# PCB1.net
KiCad netlist of a schematic drawn in EAGLE
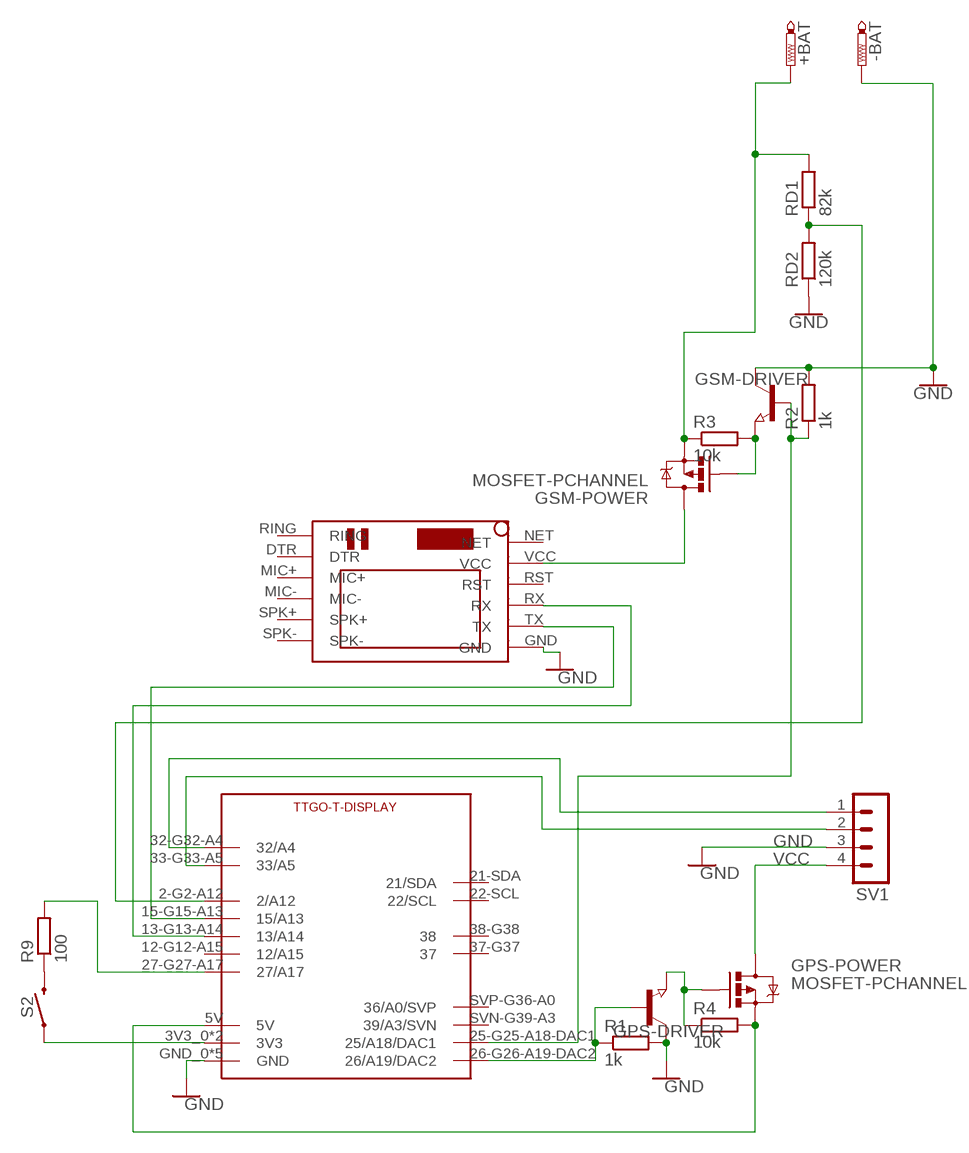
[diagram p0: schematic, sheet 1]

(export (version "E")
  (design (tool "Eeschema 10.0.6"))
  (components
    (comp (ref "+BAT")
      (value "PTR1PAD1-13Y")
      (footprint "eagle-import:P1-13Y")
      (libsource (lib "eagle-import") (part "PTR1PAD1-13Y"))
    )
    (comp (ref "-BAT")
      (value "PTR1PAD1-13Y")
      (footprint "eagle-import:P1-13Y")
      (libsource (lib "eagle-import") (part "PTR1PAD1-13Y"))
    )
    (comp (ref "GPS-DRIVER")
      (value "NPN-TRANSISTOR_SOT23")
      (footprint "eagle-import:SOT23")
      (libsource (lib "eagle-import") (part "NPN-TRANSISTOR_SOT23"))
    )
    (comp (ref "GPS-POWER")
      (value "MOSFET-PCHANNEL")
      (footprint "eagle-import:SOT23-3")
      (libsource (lib "eagle-import") (part "MOSFET-PCHANNEL"))
    )
    (comp (ref "GSM-DRIVER")
      (value "NPN-TRANSISTOR_SOT23")
      (footprint "eagle-import:SOT23")
      (libsource (lib "eagle-import") (part "NPN-TRANSISTOR_SOT23"))
    )
    (comp (ref "GSM-POWER")
      (value "MOSFET-PCHANNEL")
      (footprint "eagle-import:SOT23-3")
      (libsource (lib "eagle-import") (part "MOSFET-PCHANNEL"))
    )
    (comp (ref "R1")
      (value "1k")
      (footprint "eagle-import:R0402")
      (libsource (lib "eagle-import") (part "RR0402"))
    )
    (comp (ref "R2")
      (value "1k")
      (footprint "eagle-import:R0402")
      (libsource (lib "eagle-import") (part "RR0402"))
    )
    (comp (ref "R3")
      (value "10k")
      (footprint "eagle-import:R0603")
      (libsource (lib "eagle-import") (part "RR0603"))
    )
    (comp (ref "R4")
      (value "10k")
      (footprint "eagle-import:R0603")
      (libsource (lib "eagle-import") (part "RR0603"))
    )
    (comp (ref "R9")
      (value "100")
      (footprint "eagle-import:R0603")
      (libsource (lib "eagle-import") (part "RR0603"))
    )
    (comp (ref "RD1")
      (value "82k")
      (footprint "eagle-import:R0402")
      (libsource (lib "eagle-import") (part "RR0402"))
    )
    (comp (ref "RD2")
      (value "120k")
      (footprint "eagle-import:R0402")
      (libsource (lib "eagle-import") (part "RR0402"))
    )
    (comp (ref "S2")
      (value "MOMENTARY-SWITCH-SPST-SMD-6.0X3.5MM")
      (footprint "eagle-import:TACTILE_SWITCH_SMD_6.0X3.5MM")
      (libsource (lib "eagle-import") (part "MOMENTARY-SWITCH-SPST-SMD-6.0X3.5MM"))
    )
    (comp (ref "SV1")
      (value "MA04-1")
      (footprint "eagle-import:MA04-1")
      (libsource (lib "eagle-import") (part "MA04-1"))
    )
    (comp (ref "U$1")
      (value "SIM800LMODULE")
      (footprint "eagle-import:SIM800LMODULE")
      (libsource (lib "eagle-import") (part "SIM800LMODULE"))
    )
    (comp (ref "U$2")
      (value "TTGO-T-DISPLAYFRAME")
      (footprint "eagle-import:TTGO-T-DISPLAY-OL")
      (libsource (lib "eagle-import") (part "TTGO-T-DISPLAYFRAME"))
    )
  )
  (nets
    (net (code "1") (name "/VCC") (class "Default")
      (node (ref "GPS-POWER") (pin "3") (pinfunction "D_3") (pintype "passive"))
      (node (ref "SV1") (pin "4") (pinfunction "4_4") (pintype "passive"))
    )
    (net (code "2") (name "GND") (class "Default")
      (node (ref "-BAT") (pin "TP") (pinfunction "TP_TP") (pintype "input"))
      (node (ref "GPS-DRIVER") (pin "3") (pinfunction "C_3") (pintype "passive"))
      (node (ref "GSM-DRIVER") (pin "3") (pinfunction "C_3") (pintype "passive"))
      (node (ref "R1") (pin "2") (pinfunction "2_2") (pintype "passive"))
      (node (ref "R2") (pin "2") (pinfunction "2_2") (pintype "passive"))
      (node (ref "RD2") (pin "1") (pinfunction "1_1") (pintype "passive"))
      (node (ref "SV1") (pin "3") (pinfunction "3_3") (pintype "passive"))
      (node (ref "U$1") (pin "GND") (pinfunction "GND_GND") (pintype "bidirectional"))
      (node (ref "U$2") (pin "GND_0") (pinfunction "GND_GND_0") (pintype "power_in"))
      (node (ref "U$2") (pin "GND_1") (pinfunction "GND_GND_1") (pintype "power_in"))
      (node (ref "U$2") (pin "GND_2") (pinfunction "GND_GND_2") (pintype "power_in"))
      (node (ref "U$2") (pin "GND_3") (pinfunction "GND_GND_3") (pintype "power_in"))
      (node (ref "U$2") (pin "GND_4") (pinfunction "GND_GND_4") (pintype "power_in"))
    )
    (net (code "3") (name "Net-(GPS-DRIVER-B)") (class "Default")
      (node (ref "GPS-DRIVER") (pin "1") (pinfunction "B_1") (pintype "passive"))
      (node (ref "R1") (pin "1") (pinfunction "1_1") (pintype "passive"))
      (node (ref "U$2") (pin "26-G26-A19-DAC2") (pinfunction "26/A19/DAC2_26-G26-A19-DAC2") (pintype "bidirectional"))
    )
    (net (code "4") (name "Net-(GPS-DRIVER-E)") (class "Default")
      (node (ref "GPS-DRIVER") (pin "2") (pinfunction "E_2") (pintype "passive"))
      (node (ref "GPS-POWER") (pin "1") (pinfunction "G_1") (pintype "passive"))
      (node (ref "R4") (pin "1") (pinfunction "1_1") (pintype "passive"))
    )
    (net (code "5") (name "Net-(GPS-POWER-S)") (class "Default")
      (node (ref "GPS-POWER") (pin "2") (pinfunction "S_2") (pintype "passive"))
      (node (ref "R4") (pin "2") (pinfunction "2_2") (pintype "passive"))
      (node (ref "U$2") (pin "5V") (pinfunction "5V_5V") (pintype "power_in"))
    )
    (net (code "6") (name "Net-(GSM-DRIVER-B)") (class "Default")
      (node (ref "GSM-DRIVER") (pin "1") (pinfunction "B_1") (pintype "passive"))
      (node (ref "R2") (pin "1") (pinfunction "1_1") (pintype "passive"))
      (node (ref "U$2") (pin "25-G25-A18-DAC1") (pinfunction "25/A18/DAC1_25-G25-A18-DAC1") (pintype "bidirectional"))
    )
    (net (code "7") (name "Net-(GSM-DRIVER-E)") (class "Default")
      (node (ref "GSM-DRIVER") (pin "2") (pinfunction "E_2") (pintype "passive"))
      (node (ref "GSM-POWER") (pin "1") (pinfunction "G_1") (pintype "passive"))
      (node (ref "R3") (pin "2") (pinfunction "2_2") (pintype "passive"))
    )
    (net (code "8") (name "Net-(GSM-POWER-D)") (class "Default")
      (node (ref "GSM-POWER") (pin "3") (pinfunction "D_3") (pintype "passive"))
      (node (ref "U$1") (pin "VCC") (pinfunction "VCC_VCC") (pintype "bidirectional"))
    )
    (net (code "9") (name "Net-(GSM-POWER-S)") (class "Default")
      (node (ref "+BAT") (pin "TP") (pinfunction "TP_TP") (pintype "input"))
      (node (ref "GSM-POWER") (pin "2") (pinfunction "S_2") (pintype "passive"))
      (node (ref "R3") (pin "1") (pinfunction "1_1") (pintype "passive"))
      (node (ref "RD1") (pin "2") (pinfunction "2_2") (pintype "passive"))
    )
    (net (code "10") (name "Net-(R9-Pad1)") (class "Default")
      (node (ref "R9") (pin "1") (pinfunction "1_1") (pintype "passive"))
      (node (ref "S2") (pin "2") (pinfunction "2_2") (pintype "passive"))
    )
    (net (code "11") (name "Net-(S2-Pad1)") (class "Default")
      (node (ref "S2") (pin "1") (pinfunction "1_1") (pintype "passive"))
      (node (ref "U$2") (pin "3V3_0") (pinfunction "3V3_3V3_0") (pintype "power_in"))
      (node (ref "U$2") (pin "3V3_1") (pinfunction "3V3_3V3_1") (pintype "power_in"))
    )
    (net (code "12") (name "Net-(U$2-2{slash}A12)") (class "Default")
      (node (ref "RD1") (pin "1") (pinfunction "1_1") (pintype "passive"))
      (node (ref "RD2") (pin "2") (pinfunction "2_2") (pintype "passive"))
      (node (ref "U$2") (pin "2-G2-A12") (pinfunction "2/A12_2-G2-A12") (pintype "bidirectional"))
    )
    (net (code "13") (name "Net-(U$2-13{slash}A14)") (class "Default")
      (node (ref "U$1") (pin "RX") (pinfunction "RX_RX") (pintype "bidirectional"))
      (node (ref "U$2") (pin "13-G13-A14") (pinfunction "13/A14_13-G13-A14") (pintype "bidirectional"))
    )
    (net (code "14") (name "Net-(U$2-15{slash}A13)") (class "Default")
      (node (ref "U$1") (pin "TX") (pinfunction "TX_TX") (pintype "bidirectional"))
      (node (ref "U$2") (pin "15-G15-A13") (pinfunction "15/A13_15-G15-A13") (pintype "bidirectional"))
    )
    (net (code "15") (name "Net-(U$2-27{slash}A17)") (class "Default")
      (node (ref "R9") (pin "2") (pinfunction "2_2") (pintype "passive"))
      (node (ref "U$2") (pin "27-G27-A17") (pinfunction "27/A17_27-G27-A17") (pintype "bidirectional"))
    )
    (net (code "16") (name "Net-(U$2-32{slash}A4)") (class "Default")
      (node (ref "SV1") (pin "1") (pinfunction "1_1") (pintype "passive"))
      (node (ref "U$2") (pin "32-G32-A4") (pinfunction "32/A4_32-G32-A4") (pintype "bidirectional"))
    )
    (net (code "17") (name "Net-(U$2-33{slash}A5)") (class "Default")
      (node (ref "SV1") (pin "2") (pinfunction "2_2") (pintype "passive"))
      (node (ref "U$2") (pin "33-G33-A5") (pinfunction "33/A5_33-G33-A5") (pintype "bidirectional"))
    )
    (net (code "18") (name "unconnected-(U$1-PadDTR)") (class "Default")
      (node (ref "U$1") (pin "DTR") (pinfunction "DTR_DTR") (pintype "bidirectional"))
    )
    (net (code "19") (name "unconnected-(U$1-PadMIC+)") (class "Default")
      (node (ref "U$1") (pin "MIC+") (pinfunction "MIC+_MIC+") (pintype "bidirectional"))
    )
    (net (code "20") (name "unconnected-(U$1-PadMIC-)") (class "Default")
      (node (ref "U$1") (pin "MIC-") (pinfunction "MIC-_MIC-") (pintype "bidirectional"))
    )
    (net (code "21") (name "unconnected-(U$1-PadNET)") (class "Default")
      (node (ref "U$1") (pin "NET") (pinfunction "NET_NET") (pintype "bidirectional"))
    )
    (net (code "22") (name "unconnected-(U$1-PadRING)") (class "Default")
      (node (ref "U$1") (pin "RING") (pinfunction "RING_RING") (pintype "bidirectional"))
    )
    (net (code "23") (name "unconnected-(U$1-PadRST)") (class "Default")
      (node (ref "U$1") (pin "RST") (pinfunction "RST_RST") (pintype "bidirectional"))
    )
    (net (code "24") (name "unconnected-(U$1-PadSPK+)") (class "Default")
      (node (ref "U$1") (pin "SPK+") (pinfunction "SPK+_SPK+") (pintype "bidirectional"))
    )
    (net (code "25") (name "unconnected-(U$1-PadSPK-)") (class "Default")
      (node (ref "U$1") (pin "SPK-") (pinfunction "SPK-_SPK-") (pintype "bidirectional"))
    )
    (net (code "26") (name "unconnected-(U$2-12{slash}A15-Pad12-G12-A15)") (class "Default")
      (node (ref "U$2") (pin "12-G12-A15") (pinfunction "12/A15_12-G12-A15") (pintype "output"))
    )
    (net (code "27") (name "unconnected-(U$2-21{slash}SDA-Pad21-SDA)") (class "Default")
      (node (ref "U$2") (pin "21-SDA") (pinfunction "21/SDA_21-SDA") (pintype "bidirectional"))
    )
    (net (code "28") (name "unconnected-(U$2-22{slash}SCL-Pad22-SCL)") (class "Default")
      (node (ref "U$2") (pin "22-SCL") (pinfunction "22/SCL_22-SCL") (pintype "bidirectional"))
    )
    (net (code "29") (name "unconnected-(U$2-36{slash}A0{slash}SVP-PadSVP-G36-A0)") (class "Default")
      (node (ref "U$2") (pin "SVP-G36-A0") (pinfunction "36/A0/SVP_SVP-G36-A0") (pintype "bidirectional"))
    )
    (net (code "30") (name "unconnected-(U$2-37-Pad37-G37)") (class "Default")
      (node (ref "U$2") (pin "37-G37") (pinfunction "37_37-G37") (pintype "bidirectional"))
    )
    (net (code "31") (name "unconnected-(U$2-38-Pad38-G38)") (class "Default")
      (node (ref "U$2") (pin "38-G38") (pinfunction "38_38-G38") (pintype "bidirectional"))
    )
    (net (code "32") (name "unconnected-(U$2-39{slash}A3{slash}SVN-PadSVN-G39-A3)") (class "Default")
      (node (ref "U$2") (pin "SVN-G39-A3") (pinfunction "39/A3/SVN_SVN-G39-A3") (pintype "bidirectional"))
    )
  )
)
